# Board.net
KiCad netlist of a schematic drawn in Altium Designer
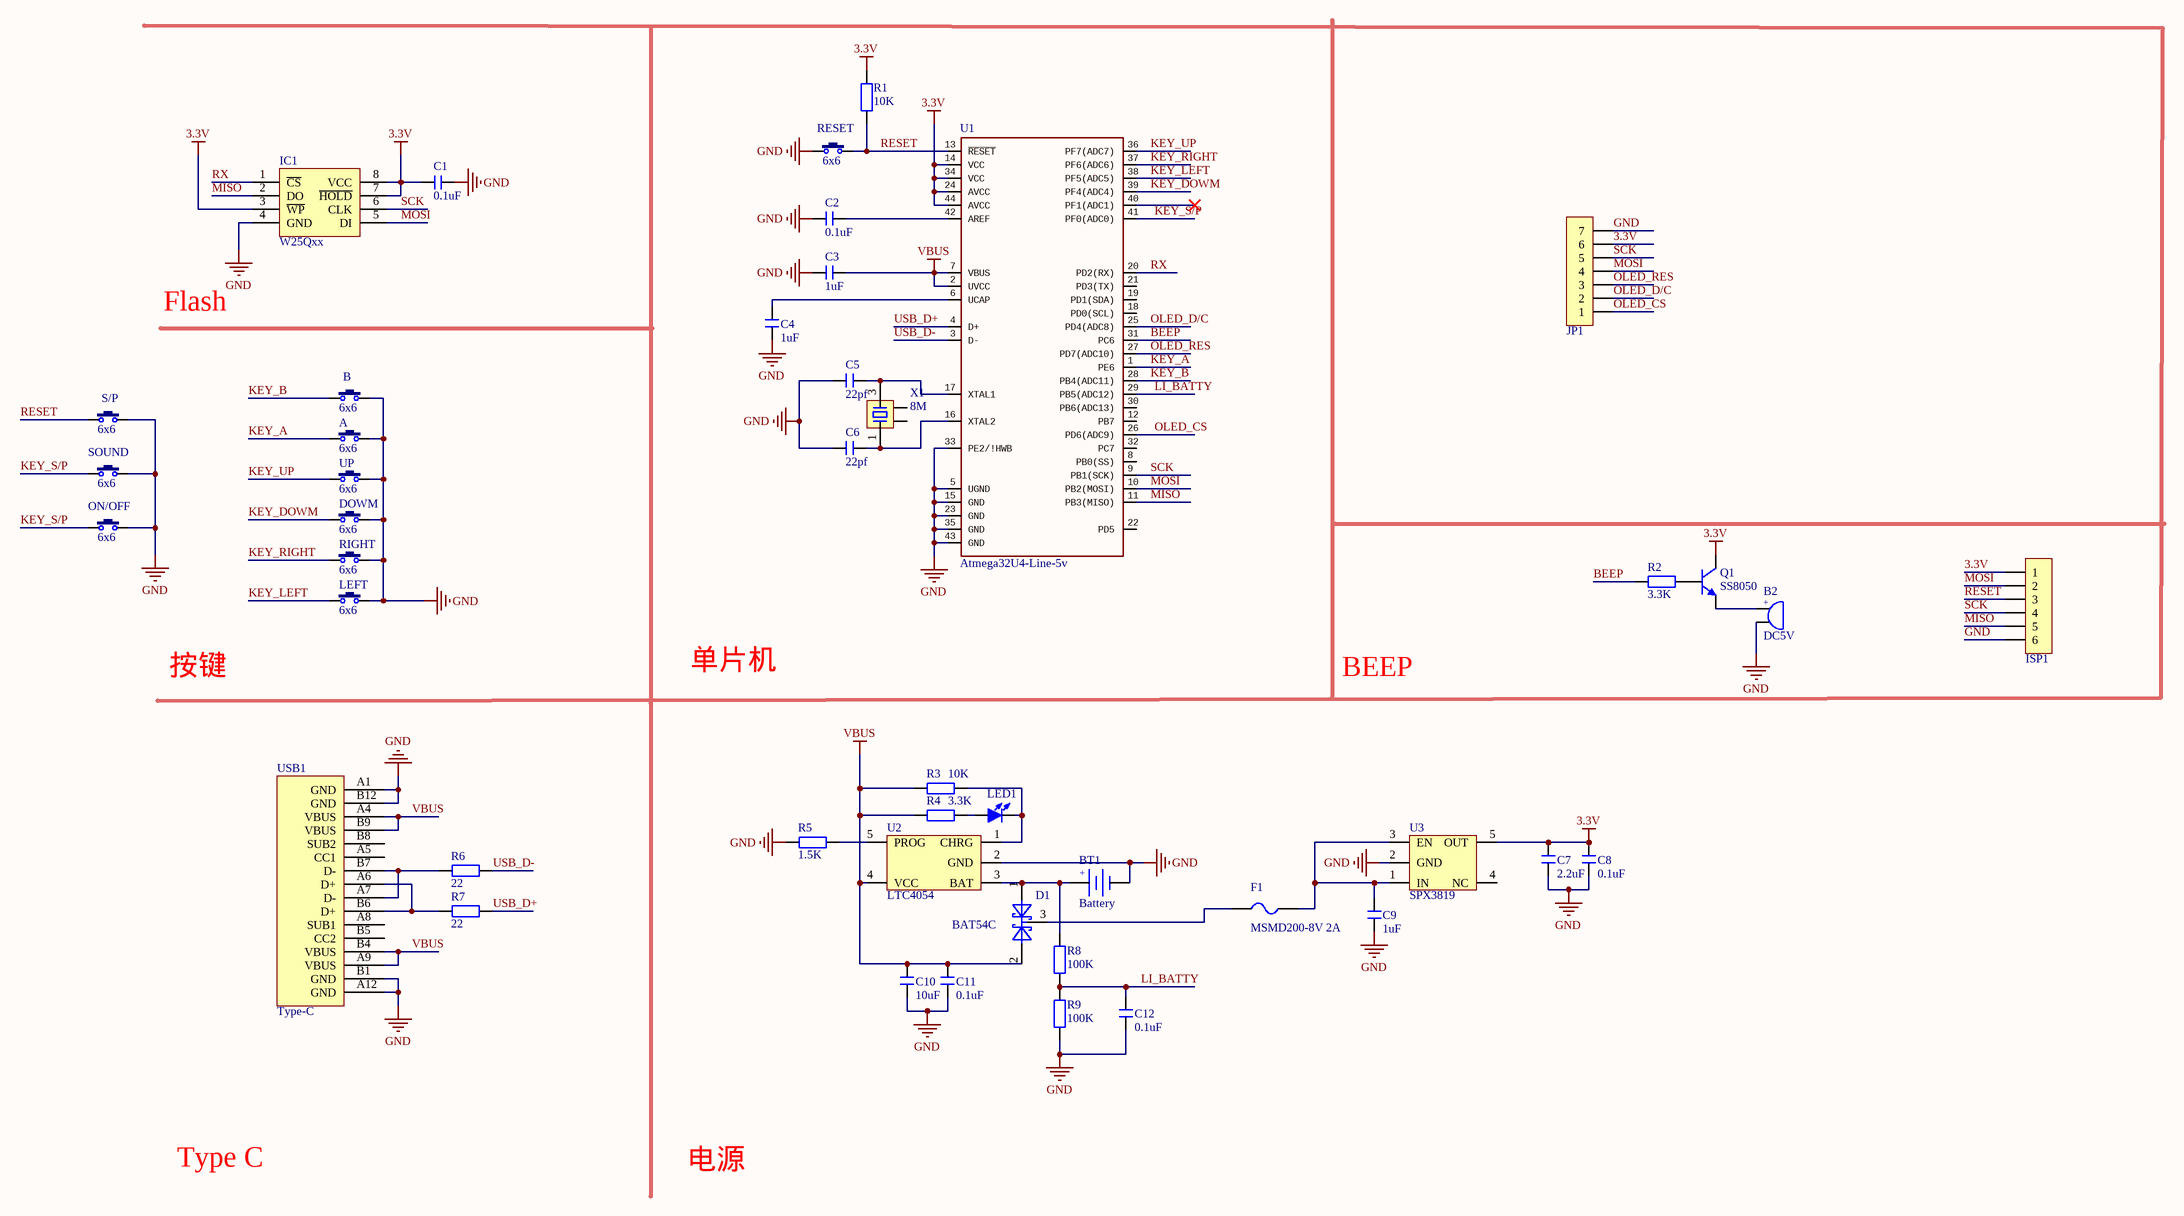
[diagram p0: Board.SchDoc]

(export (version "E")
  (design (tool "Eeschema 10.0.6"))
  (components
    (comp (ref "A")
      (value "6x6")
      (footprint "Touch key 2")
      (description "Arduboy 用")
      (libsource (lib "按键-开关") (part "SW SMD-2"))
    )
    (comp (ref "B")
      (value "6x6")
      (footprint "Touch key 2")
      (description "Arduboy 用")
      (libsource (lib "按键-开关") (part "SW SMD-2"))
    )
    (comp (ref "B2")
      (value "DC5V")
      (footprint "BEEP-SMD 5x5x2")
      (description "蜂鸣器")
      (fields (field (name "版权归属") "黎明电子style"))
      (libsource (lib "未分类器件") (part "BEEP"))
    )
    (comp (ref "BT1")
      (value "Battery")
      (footprint "Li-Bettery SMD")
      (description "锂电池")
      (libsource (lib "未分类器件") (part "Battery"))
    )
    (comp (ref "C1")
      (value "0.1uF")
      (footprint "C 0603")
      (description "无极性贴片电容")
      (fields (field (name "版权归属") "黎明电子style"))
      (libsource (lib "电阻-电容-电感") (part "C"))
    )
    (comp (ref "C2")
      (value "0.1uF")
      (footprint "C 0603")
      (description "无极性贴片电容")
      (fields (field (name "版权归属") "黎明电子style"))
      (libsource (lib "电阻-电容-电感") (part "C"))
    )
    (comp (ref "C3")
      (value "1uF")
      (footprint "C 0603")
      (description "无极性贴片电容")
      (fields (field (name "版权归属") "黎明电子style"))
      (libsource (lib "电阻-电容-电感") (part "C"))
    )
    (comp (ref "C4")
      (value "1uF")
      (footprint "C 0603")
      (description "无极性贴片电容")
      (fields (field (name "版权归属") "黎明电子style"))
      (libsource (lib "电阻-电容-电感") (part "C"))
    )
    (comp (ref "C5")
      (value "22pf")
      (footprint "C 0603")
      (description "无极性贴片电容")
      (fields (field (name "版权归属") "黎明电子style"))
      (libsource (lib "电阻-电容-电感") (part "C"))
    )
    (comp (ref "C6")
      (value "22pf")
      (footprint "C 0603")
      (description "无极性贴片电容")
      (fields (field (name "版权归属") "黎明电子style"))
      (libsource (lib "电阻-电容-电感") (part "C"))
    )
    (comp (ref "C7")
      (value "2.2uF")
      (footprint "C 0603")
      (description "无极性贴片电容")
      (fields (field (name "版权归属") "黎明电子style"))
      (libsource (lib "电阻-电容-电感") (part "C"))
    )
    (comp (ref "C8")
      (value "0.1uF")
      (footprint "C 0603")
      (description "无极性贴片电容")
      (fields (field (name "版权归属") "黎明电子style"))
      (libsource (lib "电阻-电容-电感") (part "C"))
    )
    (comp (ref "C9")
      (value "1uF")
      (footprint "C 0603")
      (description "无极性贴片电容")
      (fields (field (name "版权归属") "黎明电子style"))
      (libsource (lib "电阻-电容-电感") (part "C"))
    )
    (comp (ref "C10")
      (value "10uF")
      (footprint "C 0603")
      (description "无极性贴片电容")
      (fields (field (name "版权归属") "黎明电子style"))
      (libsource (lib "电阻-电容-电感") (part "C"))
    )
    (comp (ref "C11")
      (value "0.1uF")
      (footprint "C 0603")
      (description "无极性贴片电容")
      (fields (field (name "版权归属") "黎明电子style"))
      (libsource (lib "电阻-电容-电感") (part "C"))
    )
    (comp (ref "C12")
      (value "0.1uF")
      (footprint "C 0603")
      (description "无极性贴片电容")
      (fields (field (name "版权归属") "黎明电子style"))
      (libsource (lib "电阻-电容-电感") (part "C"))
    )
    (comp (ref "D1")
      (value "BAT54C")
      (footprint "SOT23-3M")
      (description "双肖基特二极管")
      (libsource (lib "二极管-整流桥") (part "BAT54C"))
    )
    (comp (ref "DOWM")
      (value "6x6")
      (footprint "Touch key 2")
      (description "Arduboy 用")
      (libsource (lib "按键-开关") (part "SW SMD-2"))
    )
    (comp (ref "F1")
      (value "MSMD200-8V 2A")
      (footprint "FU 0603")
      (description "贴片保险丝")
      (fields (field (name "版权归属") "黎明电子style"))
      (libsource (lib "保险丝-晶振") (part "FU"))
    )
    (comp (ref "IC1")
      (value "W25Qxx")
      (footprint "SOP8W_N")
      (description "外置Flash")
      (fields (field (name "版权归属") "黎明电子style"))
      (libsource (lib "IC芯片") (part "W25Qxx"))
    )
    (comp (ref "ISP1")
      (value "HDR-1X6")
      (footprint "IPS")
      (description "6P接插件")
      (fields (field (name "版权归属") "黎明电子style"))
      (libsource (lib "接插件") (part "Header 6"))
    )
    (comp (ref "JP1")
      (value "HDR-1X7")
      (footprint "HDR-1X7")
      (description "7P接插件")
      (fields (field (name "版权归属") "黎明电子style"))
      (libsource (lib "接插件") (part "Header 7"))
    )
    (comp (ref "LED1")
      (value "~")
      (footprint "LED 0603B")
      (description "贴片LED")
      (fields (field (name "版权归属") "黎明电子style"))
      (libsource (lib "LED") (part "LED-SMD"))
    )
    (comp (ref "LEFT")
      (value "6x6")
      (footprint "Touch key 2")
      (description "Arduboy 用")
      (libsource (lib "按键-开关") (part "SW SMD-2"))
    )
    (comp (ref "ON/OFF")
      (value "6x6")
      (footprint "Touch key 2")
      (description "Arduboy 用")
      (libsource (lib "按键-开关") (part "SW SMD-2"))
    )
    (comp (ref "Q1")
      (value "SS8050")
      (footprint "SOT23-3M")
      (description "高频放大-NPN型")
      (fields (field (name "版权归属") "黎明电子style"))
      (libsource (lib "三极管") (part "8050-SMD"))
    )
    (comp (ref "R1")
      (value "10K")
      (footprint "R 0603")
      (description "贴片电阻")
      (fields (field (name "版权归属") "黎明电子style"))
      (libsource (lib "电阻-电容-电感") (part "R"))
    )
    (comp (ref "R2")
      (value "3.3K")
      (footprint "R 0603")
      (description "贴片电阻")
      (fields (field (name "版权归属") "黎明电子style"))
      (libsource (lib "电阻-电容-电感") (part "R"))
    )
    (comp (ref "R3")
      (value "10K")
      (footprint "R 0603")
      (description "贴片电阻")
      (fields (field (name "版权归属") "黎明电子style"))
      (libsource (lib "电阻-电容-电感") (part "R"))
    )
    (comp (ref "R4")
      (value "3.3K")
      (footprint "R 0603")
      (description "贴片电阻")
      (fields (field (name "版权归属") "黎明电子style"))
      (libsource (lib "电阻-电容-电感") (part "R"))
    )
    (comp (ref "R5")
      (value "1.5K")
      (footprint "R 0603")
      (description "贴片电阻")
      (fields (field (name "版权归属") "黎明电子style"))
      (libsource (lib "电阻-电容-电感") (part "R"))
    )
    (comp (ref "R6")
      (value "22")
      (footprint "R 0603")
      (description "贴片电阻")
      (fields (field (name "版权归属") "黎明电子style"))
      (libsource (lib "电阻-电容-电感") (part "R"))
    )
    (comp (ref "R7")
      (value "22")
      (footprint "R 0603")
      (description "贴片电阻")
      (fields (field (name "版权归属") "黎明电子style"))
      (libsource (lib "电阻-电容-电感") (part "R"))
    )
    (comp (ref "R8")
      (value "100K")
      (footprint "R 0603")
      (description "贴片电阻")
      (fields (field (name "版权归属") "黎明电子style"))
      (libsource (lib "电阻-电容-电感") (part "R"))
    )
    (comp (ref "R9")
      (value "100K")
      (footprint "R 0603")
      (description "贴片电阻")
      (fields (field (name "版权归属") "黎明电子style"))
      (libsource (lib "电阻-电容-电感") (part "R"))
    )
    (comp (ref "RESET")
      (value "6x6")
      (footprint "Touch key 2")
      (description "Arduboy 用")
      (libsource (lib "按键-开关") (part "SW SMD-2"))
    )
    (comp (ref "RIGHT")
      (value "6x6")
      (footprint "Touch key 2")
      (description "Arduboy 用")
      (libsource (lib "按键-开关") (part "SW SMD-2"))
    )
    (comp (ref "S/P")
      (value "6x6")
      (footprint "Touch key 2")
      (description "Arduboy 用")
      (libsource (lib "按键-开关") (part "SW SMD-2"))
    )
    (comp (ref "SOUND")
      (value "6x6")
      (footprint "Touch key 2")
      (description "Arduboy 用")
      (libsource (lib "按键-开关") (part "SW SMD-2"))
    )
    (comp (ref "U1")
      (value "Atmega32U4-Line-5v")
      (footprint "LQFP-QFN")
      (libsource (lib "Atmel系列单片机") (part "Atmega32U4-Line-5v"))
    )
    (comp (ref "U2")
      (value "LTC4054")
      (footprint "SOT23-5M")
      (description "充电管理")
      (libsource (lib "IC芯片") (part "LTC4054"))
    )
    (comp (ref "U3")
      (value "SPX3819")
      (footprint "SOT23-5M")
      (description "3.3V LDO 稳压")
      (libsource (lib "IC芯片") (part "SPX3819"))
    )
    (comp (ref "UP")
      (value "6x6")
      (footprint "Touch key 2")
      (description "Arduboy 用")
      (libsource (lib "按键-开关") (part "SW SMD-2"))
    )
    (comp (ref "USB1")
      (value "Type-C")
      (footprint "Type C 16p")
      (description "USB 3.1  单排16PIN四脚插板(L=7.35) 一体式MD")
      (libsource (lib "接口类") (part "Type-C Socket"))
    )
    (comp (ref "X1")
      (value "8M")
      (footprint "XTAL-3225")
      (description "4脚晶振")
      (fields (field (name "版权归属") "黎明电子style"))
      (libsource (lib "保险丝-晶振") (part "XTAL-4"))
    )
  )
  (nets
    (net (code "1") (name "/BEEP") (class "Default")
      (node (ref "R2") (pin "1") (pinfunction "1_1") (pintype "passive"))
      (node (ref "U1") (pin "31") (pinfunction "PC6_31") (pintype "passive"))
    )
    (net (code "2") (name "/KEY_A") (class "Default")
      (node (ref "A") (pin "1") (pinfunction "1_1") (pintype "passive"))
      (node (ref "U1") (pin "1") (pinfunction "PE6_1") (pintype "passive"))
    )
    (net (code "3") (name "/KEY_B") (class "Default")
      (node (ref "B") (pin "1") (pinfunction "1_1") (pintype "passive"))
      (node (ref "U1") (pin "28") (pinfunction "PB4(ADC11)_28") (pintype "passive"))
    )
    (net (code "4") (name "/KEY_DOWM") (class "Default")
      (node (ref "DOWM") (pin "1") (pinfunction "1_1") (pintype "passive"))
      (node (ref "U1") (pin "39") (pinfunction "PF4(ADC4)_39") (pintype "passive"))
    )
    (net (code "5") (name "/KEY_LEFT") (class "Default")
      (node (ref "LEFT") (pin "1") (pinfunction "1_1") (pintype "passive"))
      (node (ref "U1") (pin "38") (pinfunction "PF5(ADC5)_38") (pintype "passive"))
    )
    (net (code "6") (name "/KEY_RIGHT") (class "Default")
      (node (ref "RIGHT") (pin "1") (pinfunction "1_1") (pintype "passive"))
      (node (ref "U1") (pin "37") (pinfunction "PF6(ADC6)_37") (pintype "passive"))
    )
    (net (code "7") (name "/KEY_S{slash}P") (class "Default")
      (node (ref "ON/OFF") (pin "1") (pinfunction "1_1") (pintype "passive"))
      (node (ref "SOUND") (pin "1") (pinfunction "1_1") (pintype "passive"))
      (node (ref "U1") (pin "41") (pinfunction "PF0(ADC0)_41") (pintype "passive"))
    )
    (net (code "8") (name "/KEY_UP") (class "Default")
      (node (ref "U1") (pin "36") (pinfunction "PF7(ADC7)_36") (pintype "passive"))
      (node (ref "UP") (pin "1") (pinfunction "1_1") (pintype "passive"))
    )
    (net (code "9") (name "/LI_BATTY") (class "Default")
      (node (ref "C12") (pin "2") (pinfunction "2_2") (pintype "passive"))
      (node (ref "R8") (pin "2") (pinfunction "2_2") (pintype "passive"))
      (node (ref "R9") (pin "1") (pinfunction "1_1") (pintype "passive"))
      (node (ref "U1") (pin "29") (pinfunction "PB5(ADC12)_29") (pintype "passive"))
    )
    (net (code "10") (name "/MISO") (class "Default")
      (node (ref "IC1") (pin "2") (pinfunction "DO_2") (pintype "passive"))
      (node (ref "ISP1") (pin "5") (pinfunction "5_5") (pintype "passive"))
      (node (ref "U1") (pin "11") (pinfunction "PB3(MISO)_11") (pintype "passive"))
    )
    (net (code "11") (name "/MOSI") (class "Default")
      (node (ref "IC1") (pin "5") (pinfunction "DI_5") (pintype "passive"))
      (node (ref "ISP1") (pin "2") (pinfunction "2_2") (pintype "passive"))
      (node (ref "JP1") (pin "4") (pinfunction "4_4") (pintype "passive"))
      (node (ref "U1") (pin "10") (pinfunction "PB2(MOSI)_10") (pintype "passive"))
    )
    (net (code "12") (name "/OLED_CS") (class "Default")
      (node (ref "JP1") (pin "1") (pinfunction "1_1") (pintype "passive"))
      (node (ref "U1") (pin "26") (pinfunction "PD6(ADC9)_26") (pintype "passive"))
    )
    (net (code "13") (name "/OLED_D{slash}C") (class "Default")
      (node (ref "JP1") (pin "2") (pinfunction "2_2") (pintype "passive"))
      (node (ref "U1") (pin "25") (pinfunction "PD4(ADC8)_25") (pintype "passive"))
    )
    (net (code "14") (name "/OLED_RES") (class "Default")
      (node (ref "JP1") (pin "3") (pinfunction "3_3") (pintype "passive"))
      (node (ref "U1") (pin "27") (pinfunction "PD7(ADC10)_27") (pintype "passive"))
    )
    (net (code "15") (name "/RESET") (class "Default")
      (node (ref "ISP1") (pin "3") (pinfunction "3_3") (pintype "passive"))
      (node (ref "R1") (pin "1") (pinfunction "1_1") (pintype "passive"))
      (node (ref "RESET") (pin "2") (pinfunction "2_2") (pintype "passive"))
      (node (ref "S/P") (pin "1") (pinfunction "1_1") (pintype "passive"))
      (node (ref "U1") (pin "13") (pinfunction "~{RESET}_13") (pintype "passive"))
    )
    (net (code "16") (name "/RX") (class "Default")
      (node (ref "IC1") (pin "1") (pinfunction "~{CS}_1") (pintype "passive"))
      (node (ref "U1") (pin "20") (pinfunction "PD2(RX)_20") (pintype "passive"))
    )
    (net (code "17") (name "/SCK") (class "Default")
      (node (ref "IC1") (pin "6") (pinfunction "CLK_6") (pintype "passive"))
      (node (ref "ISP1") (pin "4") (pinfunction "4_4") (pintype "passive"))
      (node (ref "JP1") (pin "5") (pinfunction "5_5") (pintype "passive"))
      (node (ref "U1") (pin "9") (pinfunction "PB1(SCK)_9") (pintype "passive"))
    )
    (net (code "18") (name "/USB_D+") (class "Default")
      (node (ref "R7") (pin "1") (pinfunction "1_1") (pintype "passive"))
      (node (ref "U1") (pin "4") (pinfunction "D+_4") (pintype "passive"))
    )
    (net (code "19") (name "/USB_D-") (class "Default")
      (node (ref "R6") (pin "1") (pinfunction "1_1") (pintype "passive"))
      (node (ref "U1") (pin "3") (pinfunction "D-_3") (pintype "passive"))
    )
    (net (code "20") (name "3.3V") (class "Default")
      (node (ref "C1") (pin "1") (pinfunction "1_1") (pintype "passive"))
      (node (ref "C7") (pin "2") (pinfunction "2_2") (pintype "passive"))
      (node (ref "C8") (pin "2") (pinfunction "2_2") (pintype "passive"))
      (node (ref "IC1") (pin "3") (pinfunction "~{WP}_3") (pintype "passive"))
      (node (ref "IC1") (pin "7") (pinfunction "~{HOLD}_7") (pintype "passive"))
      (node (ref "IC1") (pin "8") (pinfunction "VCC_8") (pintype "passive"))
      (node (ref "ISP1") (pin "1") (pinfunction "1_1") (pintype "passive"))
      (node (ref "JP1") (pin "6") (pinfunction "6_6") (pintype "passive"))
      (node (ref "Q1") (pin "3") (pinfunction "C_3") (pintype "passive"))
      (node (ref "R1") (pin "2") (pinfunction "2_2") (pintype "passive"))
      (node (ref "U1") (pin "14") (pinfunction "VCC_14") (pintype "passive"))
      (node (ref "U1") (pin "24") (pinfunction "AVCC_24") (pintype "passive"))
      (node (ref "U1") (pin "34") (pinfunction "VCC_34") (pintype "passive"))
      (node (ref "U1") (pin "44") (pinfunction "AVCC_44") (pintype "passive"))
      (node (ref "U3") (pin "5") (pinfunction "OUT_5") (pintype "passive"))
    )
    (net (code "21") (name "GND") (class "Default")
      (node (ref "A") (pin "2") (pinfunction "2_2") (pintype "passive"))
      (node (ref "B") (pin "2") (pinfunction "2_2") (pintype "passive"))
      (node (ref "B2") (pin "2") (pinfunction "2_2") (pintype "passive"))
      (node (ref "BT1") (pin "2") (pintype "passive"))
      (node (ref "C1") (pin "2") (pinfunction "2_2") (pintype "passive"))
      (node (ref "C10") (pin "1") (pinfunction "1_1") (pintype "passive"))
      (node (ref "C11") (pin "1") (pinfunction "1_1") (pintype "passive"))
      (node (ref "C12") (pin "1") (pinfunction "1_1") (pintype "passive"))
      (node (ref "C2") (pin "1") (pinfunction "1_1") (pintype "passive"))
      (node (ref "C3") (pin "1") (pinfunction "1_1") (pintype "passive"))
      (node (ref "C4") (pin "2") (pinfunction "2_2") (pintype "passive"))
      (node (ref "C5") (pin "1") (pinfunction "1_1") (pintype "passive"))
      (node (ref "C6") (pin "1") (pinfunction "1_1") (pintype "passive"))
      (node (ref "C7") (pin "1") (pinfunction "1_1") (pintype "passive"))
      (node (ref "C8") (pin "1") (pinfunction "1_1") (pintype "passive"))
      (node (ref "C9") (pin "1") (pinfunction "1_1") (pintype "passive"))
      (node (ref "DOWM") (pin "2") (pinfunction "2_2") (pintype "passive"))
      (node (ref "IC1") (pin "4") (pinfunction "GND_4") (pintype "passive"))
      (node (ref "ISP1") (pin "6") (pinfunction "6_6") (pintype "passive"))
      (node (ref "JP1") (pin "7") (pinfunction "7_7") (pintype "passive"))
      (node (ref "LEFT") (pin "2") (pinfunction "2_2") (pintype "passive"))
      (node (ref "ON/OFF") (pin "2") (pinfunction "2_2") (pintype "passive"))
      (node (ref "R5") (pin "2") (pinfunction "2_2") (pintype "passive"))
      (node (ref "R9") (pin "2") (pinfunction "2_2") (pintype "passive"))
      (node (ref "RESET") (pin "1") (pinfunction "1_1") (pintype "passive"))
      (node (ref "RIGHT") (pin "2") (pinfunction "2_2") (pintype "passive"))
      (node (ref "S/P") (pin "2") (pinfunction "2_2") (pintype "passive"))
      (node (ref "SOUND") (pin "2") (pinfunction "2_2") (pintype "passive"))
      (node (ref "U1") (pin "15") (pinfunction "GND_15") (pintype "passive"))
      (node (ref "U1") (pin "23") (pinfunction "GND_23") (pintype "passive"))
      (node (ref "U1") (pin "33") (pinfunction "PE2/!HWB_33") (pintype "passive"))
      (node (ref "U1") (pin "35") (pinfunction "GND_35") (pintype "passive"))
      (node (ref "U1") (pin "43") (pinfunction "GND_43") (pintype "passive"))
      (node (ref "U1") (pin "5") (pinfunction "UGND_5") (pintype "passive"))
      (node (ref "U2") (pin "2") (pinfunction "GND_2") (pintype "passive"))
      (node (ref "U3") (pin "2") (pinfunction "GND_2") (pintype "passive"))
      (node (ref "UP") (pin "2") (pinfunction "2_2") (pintype "passive"))
      (node (ref "USB1") (pin "A1") (pinfunction "GND_A1") (pintype "passive"))
      (node (ref "USB1") (pin "A12") (pinfunction "GND_A12") (pintype "passive"))
      (node (ref "USB1") (pin "B1") (pinfunction "GND_B1") (pintype "passive"))
      (node (ref "USB1") (pin "B12") (pinfunction "GND_B12") (pintype "passive"))
    )
    (net (code "22") (name "Net-(D1-Pad3)") (class "Default")
      (node (ref "D1") (pin "3") (pintype "passive"))
      (node (ref "F1") (pin "1") (pinfunction "1_1") (pintype "passive"))
    )
    (net (code "23") (name "Net-(LED1-A)") (class "Default")
      (node (ref "LED1") (pin "1") (pinfunction "A_1") (pintype "passive"))
      (node (ref "R4") (pin "1") (pinfunction "1_1") (pintype "passive"))
    )
    (net (code "24") (name "Net-(LED1-K)") (class "Default")
      (node (ref "LED1") (pin "2") (pinfunction "K_2") (pintype "passive"))
      (node (ref "R3") (pin "2") (pinfunction "2_2") (pintype "passive"))
      (node (ref "U2") (pin "1") (pinfunction "CHRG_1") (pintype "passive"))
    )
    (net (code "25") (name "Net-(Q1-B)") (class "Default")
      (node (ref "Q1") (pin "1") (pinfunction "B_1") (pintype "passive"))
      (node (ref "R2") (pin "2") (pinfunction "2_2") (pintype "passive"))
    )
    (net (code "26") (name "Net-(Q1-E)") (class "Default")
      (node (ref "B2") (pin "1") (pinfunction "1_1") (pintype "passive"))
      (node (ref "Q1") (pin "2") (pinfunction "E_2") (pintype "passive"))
    )
    (net (code "27") (name "Net-(R6-Pad2)") (class "Default")
      (node (ref "R6") (pin "2") (pinfunction "2_2") (pintype "passive"))
      (node (ref "USB1") (pin "A7") (pinfunction "D-_A7") (pintype "passive"))
      (node (ref "USB1") (pin "B7") (pinfunction "D-_B7") (pintype "passive"))
    )
    (net (code "28") (name "Net-(R7-Pad2)") (class "Default")
      (node (ref "R7") (pin "2") (pinfunction "2_2") (pintype "passive"))
      (node (ref "USB1") (pin "A6") (pinfunction "D+_A6") (pintype "passive"))
      (node (ref "USB1") (pin "B6") (pinfunction "D+_B6") (pintype "passive"))
    )
    (net (code "29") (name "Net-(U1-AREF)") (class "Default")
      (node (ref "C2") (pin "2") (pinfunction "2_2") (pintype "passive"))
      (node (ref "U1") (pin "42") (pinfunction "AREF_42") (pintype "passive"))
    )
    (net (code "30") (name "Net-(U1-UCAP)") (class "Default")
      (node (ref "C4") (pin "1") (pinfunction "1_1") (pintype "passive"))
      (node (ref "U1") (pin "6") (pinfunction "UCAP_6") (pintype "passive"))
    )
    (net (code "31") (name "Net-(U1-XTAL1)") (class "Default")
      (node (ref "C5") (pin "2") (pinfunction "2_2") (pintype "passive"))
      (node (ref "U1") (pin "17") (pinfunction "XTAL1_17") (pintype "passive"))
      (node (ref "X1") (pin "3") (pinfunction "3_3") (pintype "passive"))
    )
    (net (code "32") (name "Net-(U1-XTAL2)") (class "Default")
      (node (ref "C6") (pin "2") (pinfunction "2_2") (pintype "passive"))
      (node (ref "U1") (pin "16") (pinfunction "XTAL2_16") (pintype "passive"))
      (node (ref "X1") (pin "1") (pinfunction "1_1") (pintype "passive"))
    )
    (net (code "33") (name "Net-(U2-BAT)") (class "Default")
      (node (ref "BT1") (pin "1") (pintype "passive"))
      (node (ref "D1") (pin "1") (pintype "passive"))
      (node (ref "R8") (pin "1") (pinfunction "1_1") (pintype "passive"))
      (node (ref "U2") (pin "3") (pinfunction "BAT_3") (pintype "passive"))
    )
    (net (code "34") (name "Net-(U2-PROG)") (class "Default")
      (node (ref "R5") (pin "1") (pinfunction "1_1") (pintype "passive"))
      (node (ref "U2") (pin "5") (pinfunction "PROG_5") (pintype "passive"))
    )
    (net (code "35") (name "Net-(U3-EN)") (class "Default")
      (node (ref "C9") (pin "2") (pinfunction "2_2") (pintype "passive"))
      (node (ref "F1") (pin "2") (pinfunction "2_2") (pintype "passive"))
      (node (ref "U3") (pin "1") (pinfunction "IN_1") (pintype "passive"))
      (node (ref "U3") (pin "3") (pinfunction "EN_3") (pintype "passive"))
    )
    (net (code "36") (name "VBUS") (class "Default")
      (node (ref "C10") (pin "2") (pinfunction "2_2") (pintype "passive"))
      (node (ref "C11") (pin "2") (pinfunction "2_2") (pintype "passive"))
      (node (ref "C3") (pin "2") (pinfunction "2_2") (pintype "passive"))
      (node (ref "D1") (pin "2") (pintype "passive"))
      (node (ref "R3") (pin "1") (pinfunction "1_1") (pintype "passive"))
      (node (ref "R4") (pin "2") (pinfunction "2_2") (pintype "passive"))
      (node (ref "U1") (pin "2") (pinfunction "UVCC_2") (pintype "passive"))
      (node (ref "U1") (pin "7") (pinfunction "VBUS_7") (pintype "passive"))
      (node (ref "U2") (pin "4") (pinfunction "VCC_4") (pintype "passive"))
      (node (ref "USB1") (pin "A4") (pinfunction "VBUS_A4") (pintype "passive"))
      (node (ref "USB1") (pin "A9") (pinfunction "VBUS_A9") (pintype "passive"))
      (node (ref "USB1") (pin "B4") (pinfunction "VBUS_B4") (pintype "passive"))
      (node (ref "USB1") (pin "B9") (pinfunction "VBUS_B9") (pintype "passive"))
    )
    (net (code "37") (name "unconnected-(U1-PB0(SS)-Pad8)") (class "Default")
      (node (ref "U1") (pin "8") (pinfunction "PB0(SS)_8") (pintype "passive"))
    )
    (net (code "38") (name "unconnected-(U1-PB6(ADC13)-Pad30)") (class "Default")
      (node (ref "U1") (pin "30") (pinfunction "PB6(ADC13)_30") (pintype "passive"))
    )
    (net (code "39") (name "unconnected-(U1-PB7-Pad12)") (class "Default")
      (node (ref "U1") (pin "12") (pinfunction "PB7_12") (pintype "passive"))
    )
    (net (code "40") (name "unconnected-(U1-PC7-Pad32)") (class "Default")
      (node (ref "U1") (pin "32") (pinfunction "PC7_32") (pintype "passive"))
    )
    (net (code "41") (name "unconnected-(U1-PD0(SCL)-Pad18)") (class "Default")
      (node (ref "U1") (pin "18") (pinfunction "PD0(SCL)_18") (pintype "passive"))
    )
    (net (code "42") (name "unconnected-(U1-PD1(SDA)-Pad19)") (class "Default")
      (node (ref "U1") (pin "19") (pinfunction "PD1(SDA)_19") (pintype "passive"))
    )
    (net (code "43") (name "unconnected-(U1-PD3(TX)-Pad21)") (class "Default")
      (node (ref "U1") (pin "21") (pinfunction "PD3(TX)_21") (pintype "passive"))
    )
    (net (code "44") (name "unconnected-(U1-PD5-Pad22)") (class "Default")
      (node (ref "U1") (pin "22") (pinfunction "PD5_22") (pintype "passive"))
    )
    (net (code "45") (name "unconnected-(U1-PF1(ADC1)-Pad40)") (class "Default")
      (node (ref "U1") (pin "40") (pinfunction "PF1(ADC1)_40") (pintype "passive+no_connect"))
    )
    (net (code "46") (name "unconnected-(U3-NC-Pad4)") (class "Default")
      (node (ref "U3") (pin "4") (pinfunction "NC_4") (pintype "passive"))
    )
    (net (code "47") (name "unconnected-(USB1-CC1-PadA5)") (class "Default")
      (node (ref "USB1") (pin "A5") (pinfunction "CC1_A5") (pintype "passive"))
    )
    (net (code "48") (name "unconnected-(USB1-CC2-PadB5)") (class "Default")
      (node (ref "USB1") (pin "B5") (pinfunction "CC2_B5") (pintype "passive"))
    )
    (net (code "49") (name "unconnected-(USB1-SUB1-PadA8)") (class "Default")
      (node (ref "USB1") (pin "A8") (pinfunction "SUB1_A8") (pintype "passive"))
    )
    (net (code "50") (name "unconnected-(USB1-SUB2-PadB8)") (class "Default")
      (node (ref "USB1") (pin "B8") (pinfunction "SUB2_B8") (pintype "passive"))
    )
    (net (code "51") (name "unconnected-(X1-Pad2)") (class "Default")
      (node (ref "X1") (pin "2") (pinfunction "2_2") (pintype "passive"))
    )
    (net (code "52") (name "unconnected-(X1-Pad4)") (class "Default")
      (node (ref "X1") (pin "4") (pinfunction "4_4") (pintype "passive"))
    )
  )
)
